# io.net
KiCad netlist of a schematic drawn in Altium Designer
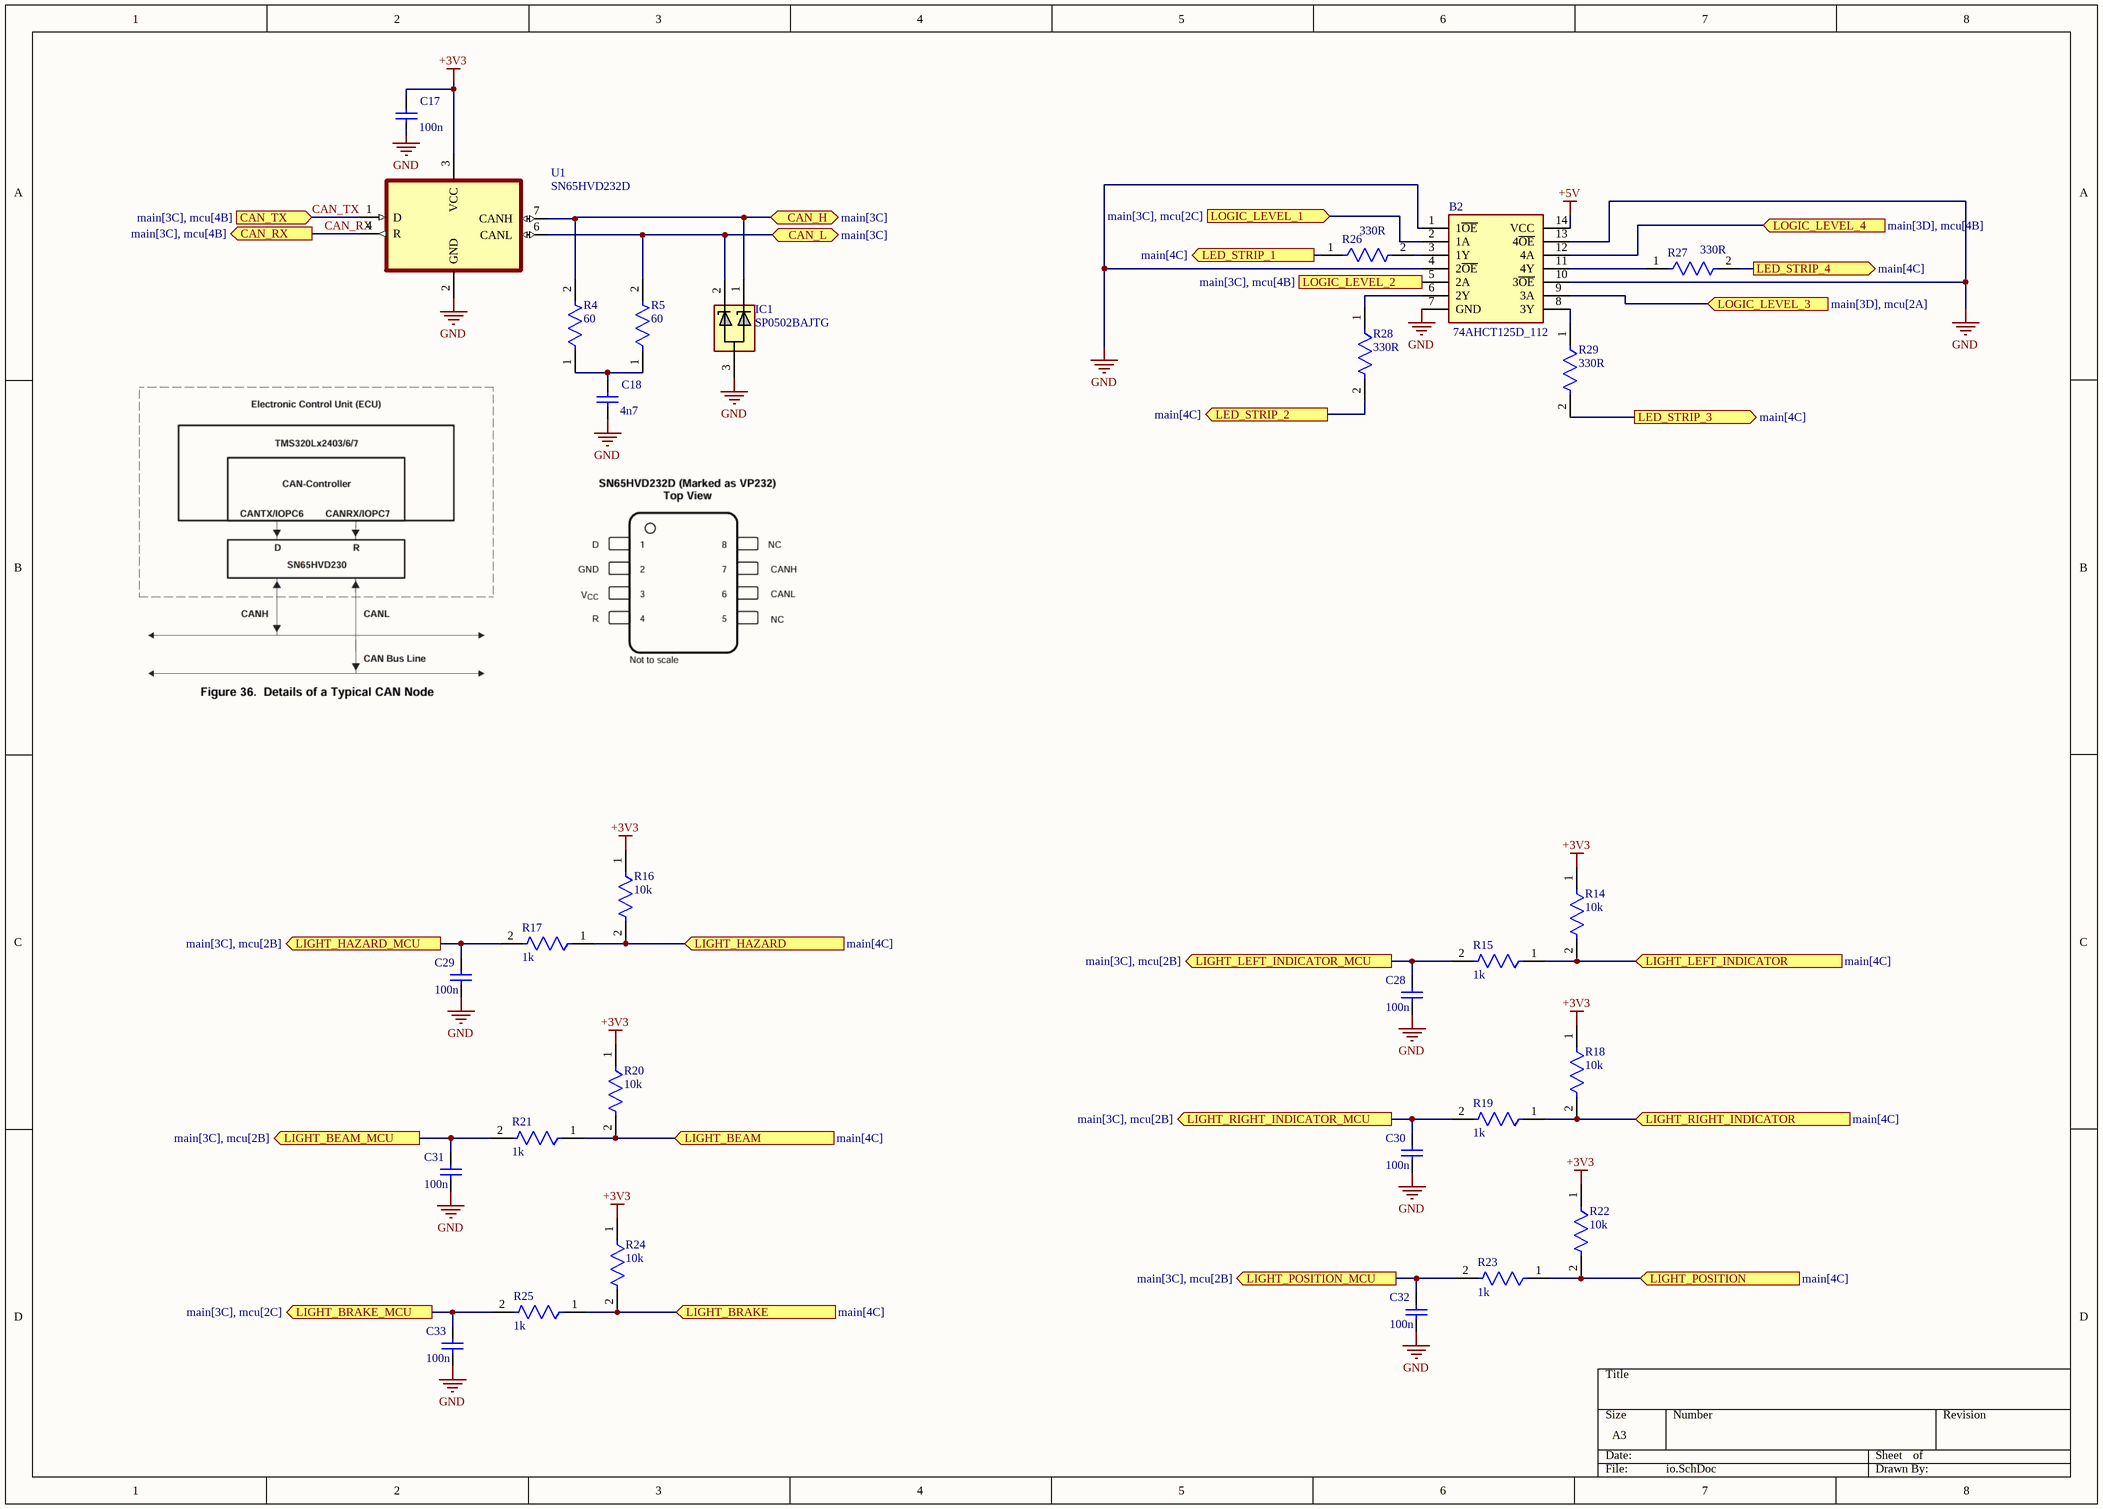
[diagram p0: io.SchDoc]

(export (version "E")
  (design (tool "Eeschema 10.0.6"))
  (components
    (comp (ref "B2")
      (value "74AHCT125D_112")
      (footprint "74AHCT125D_112")
      (description "74AHC(T)125 - Quad buffer/line driver; 3-state@en-us")
      (fields
        (field (name "MANUFACTURER_PART_NUMBER") "74AHCT125D,112")
        (field (name "MOUSER PART NUMBER") "771-AHCT125D112")
      )
      (libsource (lib "HydrogreenLibrary") (part "74AHCT125D_112"))
    )
    (comp (ref "C17")
      (value "100n")
      (footprint "CAPC1206(3216)150_L")
      (description "CAP 1.8uF 10V ±5% 1206 (3216 Metric) Thickness 1.45mm SMD")
      (fields (field (name "TOLERANCE") "Â±5%"))
      (libsource (lib "Altium Content Vault") (part "CAP"))
    )
    (comp (ref "C18")
      (value "4n7")
      (footprint "CAPC1206(3216)150_L")
      (description "CAP 1.8uF 10V ±5% 1206 (3216 Metric) Thickness 1.45mm SMD")
      (fields (field (name "TOLERANCE") "Â±5%"))
      (libsource (lib "Altium Content Vault") (part "CAP"))
    )
    (comp (ref "C28")
      (value "100n")
      (footprint "CAPC1206(3216)150_L")
      (description "CAP 1.8uF 10V ±5% 1206 (3216 Metric) Thickness 1.45mm SMD")
      (fields (field (name "TOLERANCE") "Â±5%"))
      (libsource (lib "Altium Content Vault") (part "CAP"))
    )
    (comp (ref "C29")
      (value "100n")
      (footprint "CAPC1206(3216)150_L")
      (description "CAP 1.8uF 10V ±5% 1206 (3216 Metric) Thickness 1.45mm SMD")
      (fields (field (name "TOLERANCE") "Â±5%"))
      (libsource (lib "Altium Content Vault") (part "CAP"))
    )
    (comp (ref "C30")
      (value "100n")
      (footprint "CAPC1206(3216)150_L")
      (description "CAP 1.8uF 10V ±5% 1206 (3216 Metric) Thickness 1.45mm SMD")
      (fields (field (name "TOLERANCE") "Â±5%"))
      (libsource (lib "Altium Content Vault") (part "CAP"))
    )
    (comp (ref "C31")
      (value "100n")
      (footprint "CAPC1206(3216)150_L")
      (description "CAP 1.8uF 10V ±5% 1206 (3216 Metric) Thickness 1.45mm SMD")
      (fields (field (name "TOLERANCE") "Â±5%"))
      (libsource (lib "Altium Content Vault") (part "CAP"))
    )
    (comp (ref "C32")
      (value "100n")
      (footprint "CAPC1206(3216)150_L")
      (description "CAP 1.8uF 10V ±5% 1206 (3216 Metric) Thickness 1.45mm SMD")
      (fields (field (name "TOLERANCE") "Â±5%"))
      (libsource (lib "Altium Content Vault") (part "CAP"))
    )
    (comp (ref "C33")
      (value "100n")
      (footprint "CAPC1206(3216)150_L")
      (description "CAP 1.8uF 10V ±5% 1206 (3216 Metric) Thickness 1.45mm SMD")
      (fields (field (name "TOLERANCE") "Â±5%"))
      (libsource (lib "Altium Content Vault") (part "CAP"))
    )
    (comp (ref "IC1")
      (value "SP0502BAJTG")
      (footprint "SOT132P220X110-3N")
      (description "Integrated Circuit")
      (fields (field (name "MOUSER PART NUMBER") "576-SP0502BAJTG"))
      (libsource (lib "HydrogreenLibrary") (part "SP0502BAJTG"))
    )
    (comp (ref "R4")
      (value "60")
      (footprint "FP-RK73H2B-MFG")
      (description "40.2kΩ ±1% 0.25W Chip Resistor 1206 Thick Film AEC-Q200 Qualified")
      (fields (field (name "TOLERANCE") "1%"))
      (libsource (lib "Altium Content Vault") (part "1029c3af85768c4190bb7ad29bc67b5"))
    )
    (comp (ref "R5")
      (value "60")
      (footprint "FP-RK73H2B-MFG")
      (description "40.2kΩ ±1% 0.25W Chip Resistor 1206 Thick Film AEC-Q200 Qualified")
      (fields (field (name "TOLERANCE") "1%"))
      (libsource (lib "Altium Content Vault") (part "1029c3af85768c4190bb7ad29bc67b5"))
    )
    (comp (ref "R14")
      (value "10k")
      (footprint "FP-RK73H2B-MFG")
      (description "40.2kΩ ±1% 0.25W Chip Resistor 1206 Thick Film AEC-Q200 Qualified")
      (fields (field (name "TOLERANCE") "1%"))
      (libsource (lib "Altium Content Vault") (part "1029c3af85768c4190bb7ad29bc67b5"))
    )
    (comp (ref "R15")
      (value "1k")
      (footprint "FP-RK73H2B-MFG")
      (description "40.2kΩ ±1% 0.25W Chip Resistor 1206 Thick Film AEC-Q200 Qualified")
      (fields (field (name "TOLERANCE") "1%"))
      (libsource (lib "Altium Content Vault") (part "1029c3af85768c4190bb7ad29bc67b5"))
    )
    (comp (ref "R16")
      (value "10k")
      (footprint "FP-RK73H2B-MFG")
      (description "40.2kΩ ±1% 0.25W Chip Resistor 1206 Thick Film AEC-Q200 Qualified")
      (fields (field (name "TOLERANCE") "1%"))
      (libsource (lib "Altium Content Vault") (part "1029c3af85768c4190bb7ad29bc67b5"))
    )
    (comp (ref "R17")
      (value "1k")
      (footprint "FP-RK73H2B-MFG")
      (description "40.2kΩ ±1% 0.25W Chip Resistor 1206 Thick Film AEC-Q200 Qualified")
      (fields (field (name "TOLERANCE") "1%"))
      (libsource (lib "Altium Content Vault") (part "1029c3af85768c4190bb7ad29bc67b5"))
    )
    (comp (ref "R18")
      (value "10k")
      (footprint "FP-RK73H2B-MFG")
      (description "40.2kΩ ±1% 0.25W Chip Resistor 1206 Thick Film AEC-Q200 Qualified")
      (fields (field (name "TOLERANCE") "1%"))
      (libsource (lib "Altium Content Vault") (part "1029c3af85768c4190bb7ad29bc67b5"))
    )
    (comp (ref "R19")
      (value "1k")
      (footprint "FP-RK73H2B-MFG")
      (description "40.2kΩ ±1% 0.25W Chip Resistor 1206 Thick Film AEC-Q200 Qualified")
      (fields (field (name "TOLERANCE") "1%"))
      (libsource (lib "Altium Content Vault") (part "1029c3af85768c4190bb7ad29bc67b5"))
    )
    (comp (ref "R20")
      (value "10k")
      (footprint "FP-RK73H2B-MFG")
      (description "40.2kΩ ±1% 0.25W Chip Resistor 1206 Thick Film AEC-Q200 Qualified")
      (fields (field (name "TOLERANCE") "1%"))
      (libsource (lib "Altium Content Vault") (part "1029c3af85768c4190bb7ad29bc67b5"))
    )
    (comp (ref "R21")
      (value "1k")
      (footprint "FP-RK73H2B-MFG")
      (description "40.2kΩ ±1% 0.25W Chip Resistor 1206 Thick Film AEC-Q200 Qualified")
      (fields (field (name "TOLERANCE") "1%"))
      (libsource (lib "Altium Content Vault") (part "1029c3af85768c4190bb7ad29bc67b5"))
    )
    (comp (ref "R22")
      (value "10k")
      (footprint "FP-RK73H2B-MFG")
      (description "40.2kΩ ±1% 0.25W Chip Resistor 1206 Thick Film AEC-Q200 Qualified")
      (fields (field (name "TOLERANCE") "1%"))
      (libsource (lib "Altium Content Vault") (part "1029c3af85768c4190bb7ad29bc67b5"))
    )
    (comp (ref "R23")
      (value "1k")
      (footprint "FP-RK73H2B-MFG")
      (description "40.2kΩ ±1% 0.25W Chip Resistor 1206 Thick Film AEC-Q200 Qualified")
      (fields (field (name "TOLERANCE") "1%"))
      (libsource (lib "Altium Content Vault") (part "1029c3af85768c4190bb7ad29bc67b5"))
    )
    (comp (ref "R24")
      (value "10k")
      (footprint "FP-RK73H2B-MFG")
      (description "40.2kΩ ±1% 0.25W Chip Resistor 1206 Thick Film AEC-Q200 Qualified")
      (fields (field (name "TOLERANCE") "1%"))
      (libsource (lib "Altium Content Vault") (part "1029c3af85768c4190bb7ad29bc67b5"))
    )
    (comp (ref "R25")
      (value "1k")
      (footprint "FP-RK73H2B-MFG")
      (description "40.2kΩ ±1% 0.25W Chip Resistor 1206 Thick Film AEC-Q200 Qualified")
      (fields (field (name "TOLERANCE") "1%"))
      (libsource (lib "Altium Content Vault") (part "1029c3af85768c4190bb7ad29bc67b5"))
    )
    (comp (ref "R26")
      (value "330R")
      (footprint "FP-RK73H2B-MFG")
      (description "40.2kΩ ±1% 0.25W Chip Resistor 1206 Thick Film AEC-Q200 Qualified")
      (fields (field (name "TOLERANCE") "1%"))
      (libsource (lib "Altium Content Vault") (part "1029c3af85768c4190bb7ad29bc67b5"))
    )
    (comp (ref "R27")
      (value "330R")
      (footprint "FP-RK73H2B-MFG")
      (description "40.2kΩ ±1% 0.25W Chip Resistor 1206 Thick Film AEC-Q200 Qualified")
      (fields (field (name "TOLERANCE") "1%"))
      (libsource (lib "Altium Content Vault") (part "1029c3af85768c4190bb7ad29bc67b5"))
    )
    (comp (ref "R28")
      (value "330R")
      (footprint "FP-RK73H2B-MFG")
      (description "40.2kΩ ±1% 0.25W Chip Resistor 1206 Thick Film AEC-Q200 Qualified")
      (fields (field (name "TOLERANCE") "1%"))
      (libsource (lib "Altium Content Vault") (part "1029c3af85768c4190bb7ad29bc67b5"))
    )
    (comp (ref "R29")
      (value "330R")
      (footprint "FP-RK73H2B-MFG")
      (description "40.2kΩ ±1% 0.25W Chip Resistor 1206 Thick Film AEC-Q200 Qualified")
      (fields (field (name "TOLERANCE") "1%"))
      (libsource (lib "Altium Content Vault") (part "1029c3af85768c4190bb7ad29bc67b5"))
    )
    (comp (ref "U1")
      (value "SN65HVD232D")
      (footprint "SN65HVD232D")
      (description "Texas Instruments - SN65HVD232DR - Can Transceiver, 1MBPS, 1/1, 3.3V, SOIC-8, Full Reel")
      (fields
        (field (name "MF") "Texas Instruments")
        (field (name "MANUFACTURER PART NUMBER") "SN65HVD232DR")
      )
      (libsource (lib "HydrogreenLibrary") (part "SN65HVD232D"))
    )
  )
  (nets
    (net (code "1") (name "+3V3") (class "Default")
      (node (ref "C17") (pin "1") (pinfunction "1_1") (pintype "passive"))
      (node (ref "R14") (pin "1") (pinfunction "1_1") (pintype "passive"))
      (node (ref "R16") (pin "1") (pinfunction "1_1") (pintype "passive"))
      (node (ref "R18") (pin "1") (pinfunction "1_1") (pintype "passive"))
      (node (ref "R20") (pin "1") (pinfunction "1_1") (pintype "passive"))
      (node (ref "R22") (pin "1") (pinfunction "1_1") (pintype "passive"))
      (node (ref "R24") (pin "1") (pinfunction "1_1") (pintype "passive"))
      (node (ref "U1") (pin "3") (pinfunction "VCC_3") (pintype "power_in"))
    )
    (net (code "2") (name "+5V") (class "Default")
      (node (ref "B2") (pin "14") (pinfunction "VCC_14") (pintype "passive"))
    )
    (net (code "3") (name "/CAN_H") (class "Default")
      (node (ref "IC1") (pin "1") (pintype "passive"))
      (node (ref "R4") (pin "2") (pinfunction "2_2") (pintype "passive"))
      (node (ref "U1") (pin "7") (pinfunction "CANH_7") (pintype "bidirectional"))
    )
    (net (code "4") (name "/CAN_L") (class "Default")
      (node (ref "IC1") (pin "2") (pintype "passive"))
      (node (ref "R5") (pin "2") (pinfunction "2_2") (pintype "passive"))
      (node (ref "U1") (pin "6") (pinfunction "CANL_6") (pintype "bidirectional"))
    )
    (net (code "5") (name "/CAN_RX") (class "Default")
      (node (ref "U1") (pin "4") (pinfunction "R_4") (pintype "output"))
    )
    (net (code "6") (name "/CAN_TX") (class "Default")
      (node (ref "U1") (pin "1") (pinfunction "D_1") (pintype "input"))
    )
    (net (code "7") (name "/LED_STRIP_1") (class "Default")
      (node (ref "R26") (pin "1") (pinfunction "1_1") (pintype "passive"))
    )
    (net (code "8") (name "/LED_STRIP_2") (class "Default")
      (node (ref "R28") (pin "2") (pinfunction "2_2") (pintype "passive"))
    )
    (net (code "9") (name "/LED_STRIP_3") (class "Default")
      (node (ref "R29") (pin "2") (pinfunction "2_2") (pintype "passive"))
    )
    (net (code "10") (name "/LED_STRIP_4") (class "Default")
      (node (ref "R27") (pin "2") (pinfunction "2_2") (pintype "passive"))
    )
    (net (code "11") (name "/LIGHT_BEAM") (class "Default")
      (node (ref "R20") (pin "2") (pinfunction "2_2") (pintype "passive"))
      (node (ref "R21") (pin "1") (pinfunction "1_1") (pintype "passive"))
    )
    (net (code "12") (name "/LIGHT_BEAM_MCU") (class "Default")
      (node (ref "C31") (pin "1") (pinfunction "1_1") (pintype "passive"))
      (node (ref "R21") (pin "2") (pinfunction "2_2") (pintype "passive"))
    )
    (net (code "13") (name "/LIGHT_BRAKE") (class "Default")
      (node (ref "R24") (pin "2") (pinfunction "2_2") (pintype "passive"))
      (node (ref "R25") (pin "1") (pinfunction "1_1") (pintype "passive"))
    )
    (net (code "14") (name "/LIGHT_BRAKE_MCU") (class "Default")
      (node (ref "C33") (pin "1") (pinfunction "1_1") (pintype "passive"))
      (node (ref "R25") (pin "2") (pinfunction "2_2") (pintype "passive"))
    )
    (net (code "15") (name "/LIGHT_HAZARD") (class "Default")
      (node (ref "R16") (pin "2") (pinfunction "2_2") (pintype "passive"))
      (node (ref "R17") (pin "1") (pinfunction "1_1") (pintype "passive"))
    )
    (net (code "16") (name "/LIGHT_HAZARD_MCU") (class "Default")
      (node (ref "C29") (pin "1") (pinfunction "1_1") (pintype "passive"))
      (node (ref "R17") (pin "2") (pinfunction "2_2") (pintype "passive"))
    )
    (net (code "17") (name "/LIGHT_LEFT_INDICATOR") (class "Default")
      (node (ref "R14") (pin "2") (pinfunction "2_2") (pintype "passive"))
      (node (ref "R15") (pin "1") (pinfunction "1_1") (pintype "passive"))
    )
    (net (code "18") (name "/LIGHT_LEFT_INDICATOR_MCU") (class "Default")
      (node (ref "C28") (pin "1") (pinfunction "1_1") (pintype "passive"))
      (node (ref "R15") (pin "2") (pinfunction "2_2") (pintype "passive"))
    )
    (net (code "19") (name "/LIGHT_POSITION") (class "Default")
      (node (ref "R22") (pin "2") (pinfunction "2_2") (pintype "passive"))
      (node (ref "R23") (pin "1") (pinfunction "1_1") (pintype "passive"))
    )
    (net (code "20") (name "/LIGHT_POSITION_MCU") (class "Default")
      (node (ref "C32") (pin "1") (pinfunction "1_1") (pintype "passive"))
      (node (ref "R23") (pin "2") (pinfunction "2_2") (pintype "passive"))
    )
    (net (code "21") (name "/LIGHT_RIGHT_INDICATOR") (class "Default")
      (node (ref "R18") (pin "2") (pinfunction "2_2") (pintype "passive"))
      (node (ref "R19") (pin "1") (pinfunction "1_1") (pintype "passive"))
    )
    (net (code "22") (name "/LIGHT_RIGHT_INDICATOR_MCU") (class "Default")
      (node (ref "C30") (pin "1") (pinfunction "1_1") (pintype "passive"))
      (node (ref "R19") (pin "2") (pinfunction "2_2") (pintype "passive"))
    )
    (net (code "23") (name "/LOGIC_LEVEL_1") (class "Default")
      (node (ref "B2") (pin "2") (pinfunction "1A_2") (pintype "passive"))
    )
    (net (code "24") (name "/LOGIC_LEVEL_2") (class "Default")
      (node (ref "B2") (pin "5") (pinfunction "2A_5") (pintype "passive"))
    )
    (net (code "25") (name "/LOGIC_LEVEL_3") (class "Default")
      (node (ref "B2") (pin "9") (pinfunction "3A_9") (pintype "passive"))
    )
    (net (code "26") (name "/LOGIC_LEVEL_4") (class "Default")
      (node (ref "B2") (pin "12") (pinfunction "4A_12") (pintype "passive"))
    )
    (net (code "27") (name "GND") (class "Default")
      (node (ref "B2") (pin "1") (pinfunction "1~{OE}_1") (pintype "passive"))
      (node (ref "B2") (pin "10") (pinfunction "3~{OE}_10") (pintype "passive"))
      (node (ref "B2") (pin "13") (pinfunction "4~{OE}_13") (pintype "passive"))
      (node (ref "B2") (pin "4") (pinfunction "2~{OE}_4") (pintype "passive"))
      (node (ref "B2") (pin "7") (pinfunction "GND_7") (pintype "passive"))
      (node (ref "C17") (pin "2") (pinfunction "2_2") (pintype "passive"))
      (node (ref "C18") (pin "2") (pinfunction "2_2") (pintype "passive"))
      (node (ref "C28") (pin "2") (pinfunction "2_2") (pintype "passive"))
      (node (ref "C29") (pin "2") (pinfunction "2_2") (pintype "passive"))
      (node (ref "C30") (pin "2") (pinfunction "2_2") (pintype "passive"))
      (node (ref "C31") (pin "2") (pinfunction "2_2") (pintype "passive"))
      (node (ref "C32") (pin "2") (pinfunction "2_2") (pintype "passive"))
      (node (ref "C33") (pin "2") (pinfunction "2_2") (pintype "passive"))
      (node (ref "IC1") (pin "3") (pintype "passive"))
      (node (ref "U1") (pin "2") (pinfunction "GND_2") (pintype "power_in"))
    )
    (net (code "28") (name "Net-(B2-1Y)") (class "Default")
      (node (ref "B2") (pin "3") (pinfunction "1Y_3") (pintype "passive"))
      (node (ref "R26") (pin "2") (pinfunction "2_2") (pintype "passive"))
    )
    (net (code "29") (name "Net-(B2-2Y)") (class "Default")
      (node (ref "B2") (pin "6") (pinfunction "2Y_6") (pintype "passive"))
      (node (ref "R28") (pin "1") (pinfunction "1_1") (pintype "passive"))
    )
    (net (code "30") (name "Net-(B2-3Y)") (class "Default")
      (node (ref "B2") (pin "8") (pinfunction "3Y_8") (pintype "passive"))
      (node (ref "R29") (pin "1") (pinfunction "1_1") (pintype "passive"))
    )
    (net (code "31") (name "Net-(B2-4Y)") (class "Default")
      (node (ref "B2") (pin "11") (pinfunction "4Y_11") (pintype "passive"))
      (node (ref "R27") (pin "1") (pinfunction "1_1") (pintype "passive"))
    )
    (net (code "32") (name "Net-(C18-Pad1)") (class "Default")
      (node (ref "C18") (pin "1") (pinfunction "1_1") (pintype "passive"))
      (node (ref "R4") (pin "1") (pinfunction "1_1") (pintype "passive"))
      (node (ref "R5") (pin "1") (pinfunction "1_1") (pintype "passive"))
    )
  )
)
